# FAT35o.net
KiCad netlist of a schematic drawn in Altium Designer
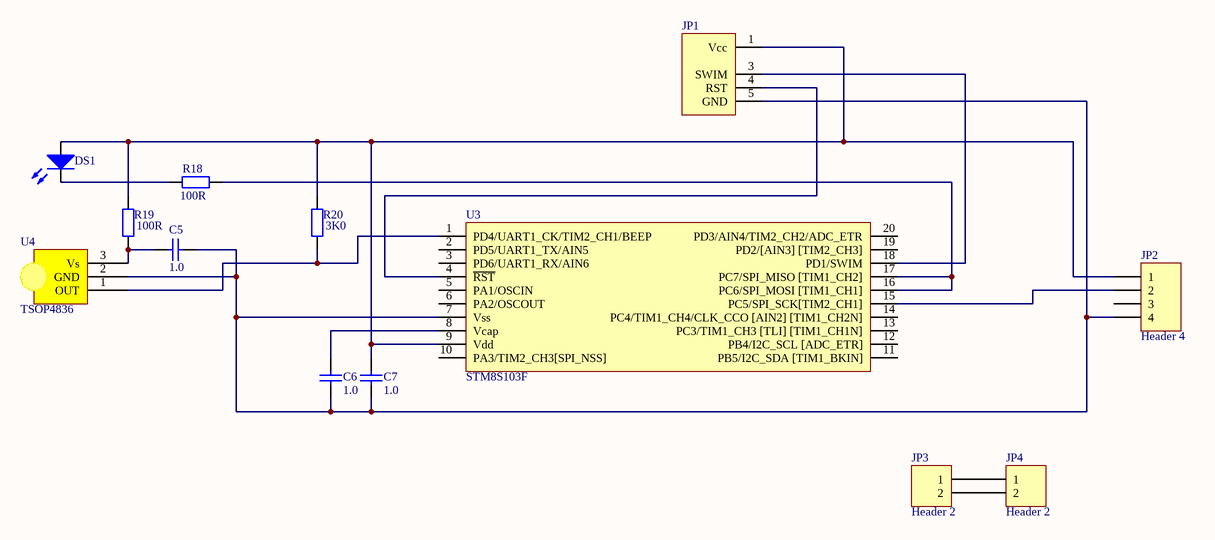
[diagram p0: FAT35o.SchDoc]

(export (version "E")
  (design (tool "Eeschema 10.0.6"))
  (components
    (comp (ref "C5")
      (value "1.0")
      (footprint "_1206")
      (description "Capacitor (Semiconductor SIM Model)")
      (fields (field (name "MANUFACTURER") "Generic Components") (field (name "PUBLISHER") "Altium Limited"))
      (libsource (lib "Miscellaneous Devices") (part "Cap Semi"))
    )
    (comp (ref "C6")
      (value "1.0")
      (footprint "_1206")
      (description "Capacitor (Semiconductor SIM Model)")
      (fields (field (name "MANUFACTURER") "Generic Components") (field (name "PUBLISHER") "Altium Limited"))
      (libsource (lib "") (part "Cap Semi_1"))
    )
    (comp (ref "C7")
      (value "1.0")
      (footprint "_1206")
      (description "Capacitor (Semiconductor SIM Model)")
      (fields (field (name "MANUFACTURER") "Generic Components") (field (name "PUBLISHER") "Altium Limited"))
      (libsource (lib "") (part "Cap Semi_1"))
    )
    (comp (ref "DS1")
      (value "~")
      (footprint "HDR1X2")
      (description "Typical INFRARED GaAs LED")
      (fields (field (name "MANUFACTURER") "Generic Components") (field (name "PUBLISHER") "Altium Limited"))
      (libsource (lib "PAL") (part "LED0"))
    )
    (comp (ref "JP1") (value "~") (footprint "HDR1X5_uart") (libsource (lib "PAL") (part "SWIM_CONN")))
    (comp (ref "JP2")
      (value "Header 4")
      (footprint "HDR2X2")
      (description "Header, 4-Pin")
      (fields (field (name "MANUFACTURER") "Generic Components") (field (name "PUBLISHER") "Altium Limited"))
      (libsource (lib "Miscellaneous Connectors") (part "Header 4"))
    )
    (comp (ref "JP3")
      (value "Header 2")
      (footprint "HDR1X2")
      (description "Header, 2-Pin")
      (fields (field (name "MANUFACTURER") "Generic Components") (field (name "PUBLISHER") "Altium Limited"))
      (libsource (lib "") (part "Header 2_1"))
    )
    (comp (ref "JP4")
      (value "Header 2")
      (footprint "HDR1X2")
      (description "Header, 2-Pin")
      (fields (field (name "MANUFACTURER") "Generic Components") (field (name "PUBLISHER") "Altium Limited"))
      (libsource (lib "Miscellaneous Connectors") (part "Header 2"))
    )
    (comp (ref "R18")
      (value "100R")
      (footprint "_1206")
      (description "Resistor")
      (fields (field (name "MANUFACTURER") "Generic Components") (field (name "PUBLISHER") "Altium Limited"))
      (libsource (lib "") (part "Res2_1"))
    )
    (comp (ref "R19")
      (value "100R")
      (footprint "_1206")
      (description "Resistor")
      (fields (field (name "MANUFACTURER") "Generic Components") (field (name "PUBLISHER") "Altium Limited"))
      (libsource (lib "Miscellaneous Devices") (part "Res2"))
    )
    (comp (ref "R20")
      (value "3K0")
      (footprint "_1206")
      (description "Resistor")
      (fields (field (name "MANUFACTURER") "Generic Components") (field (name "PUBLISHER") "Altium Limited"))
      (libsource (lib "Miscellaneous Devices") (part "Res2"))
    )
    (comp (ref "U3") (value "~") (footprint "TSSO6x6-G20/Y1.6") (libsource (lib "PAL") (part "STM8S103F")))
    (comp (ref "U4") (value "TSOP4836") (footprint "TSOP4836") (libsource (lib "PAL") (part "TSOP4836")))
  )
  (nets
    (net (code "1") (name "Net-(DS1-A)") (class "Default")
      (node (ref "C7") (pin "2") (pinfunction "2_2") (pintype "passive"))
      (node (ref "DS1") (pin "1") (pinfunction "A_1") (pintype "passive"))
      (node (ref "JP1") (pin "1") (pinfunction "Vcc_1") (pintype "passive"))
      (node (ref "JP2") (pin "1") (pinfunction "1_1") (pintype "passive"))
      (node (ref "R19") (pin "1") (pinfunction "1_1") (pintype "passive"))
      (node (ref "R20") (pin "1") (pinfunction "1_1") (pintype "passive"))
      (node (ref "U3") (pin "9") (pinfunction "Vdd_9") (pintype "passive"))
    )
    (net (code "2") (name "Net-(DS1-K)") (class "Default")
      (node (ref "DS1") (pin "2") (pinfunction "K_2") (pintype "passive"))
      (node (ref "R18") (pin "2") (pinfunction "2_2") (pintype "passive"))
    )
    (net (code "3") (name "Net-(JP1-GND)") (class "Default")
      (node (ref "C5") (pin "1") (pinfunction "1_1") (pintype "passive"))
      (node (ref "C6") (pin "1") (pinfunction "1_1") (pintype "passive"))
      (node (ref "C7") (pin "1") (pinfunction "1_1") (pintype "passive"))
      (node (ref "JP1") (pin "5") (pinfunction "GND_5") (pintype "passive"))
      (node (ref "JP2") (pin "4") (pinfunction "4_4") (pintype "passive"))
      (node (ref "U3") (pin "7") (pinfunction "Vss_7") (pintype "passive"))
      (node (ref "U4") (pin "2") (pinfunction "GND_2") (pintype "passive"))
    )
    (net (code "4") (name "Net-(JP1-RST)") (class "Default")
      (node (ref "JP1") (pin "4") (pinfunction "RST_4") (pintype "passive"))
      (node (ref "U3") (pin "4") (pinfunction "~{RST}_4") (pintype "passive"))
    )
    (net (code "5") (name "Net-(JP1-SWIM)") (class "Default")
      (node (ref "JP1") (pin "3") (pinfunction "SWIM_3") (pintype "passive"))
      (node (ref "U3") (pin "18") (pinfunction "PD1/SWIM_18") (pintype "passive"))
    )
    (net (code "6") (name "Net-(JP3-Pad1)") (class "Default")
      (node (ref "JP3") (pin "1") (pinfunction "1_1") (pintype "passive"))
      (node (ref "JP4") (pin "1") (pinfunction "1_1") (pintype "passive"))
    )
    (net (code "7") (name "Net-(JP3-Pad2)") (class "Default")
      (node (ref "JP3") (pin "2") (pinfunction "2_2") (pintype "passive"))
      (node (ref "JP4") (pin "2") (pinfunction "2_2") (pintype "passive"))
    )
    (net (code "8") (name "Net-(U3-PC5{slash}SPI_SCK[TIM2_CH1])") (class "Default")
      (node (ref "JP2") (pin "2") (pinfunction "2_2") (pintype "passive"))
      (node (ref "U3") (pin "15") (pinfunction "PC5/SPI_SCK[TIM2_CH1]_15") (pintype "passive"))
    )
    (net (code "9") (name "Net-(U3-PC6{slash}SPI_MOSI_[TIM1_CH1])") (class "Default")
      (node (ref "R18") (pin "1") (pinfunction "1_1") (pintype "passive"))
      (node (ref "U3") (pin "16") (pinfunction "PC6/SPI_MOSI_[TIM1_CH1]_16") (pintype "passive"))
      (node (ref "U3") (pin "17") (pinfunction "PC7/SPI_MISO_[TIM1_CH2]_17") (pintype "passive"))
    )
    (net (code "10") (name "Net-(U3-PD4{slash}UART1_CK{slash}TIM2_CH1{slash}BEEP)") (class "Default")
      (node (ref "R20") (pin "2") (pinfunction "2_2") (pintype "passive"))
      (node (ref "U3") (pin "1") (pinfunction "PD4/UART1_CK/TIM2_CH1/BEEP_1") (pintype "passive"))
      (node (ref "U4") (pin "1") (pinfunction "OUT_1") (pintype "passive"))
    )
    (net (code "11") (name "Net-(U3-Vcap)") (class "Default")
      (node (ref "C6") (pin "2") (pinfunction "2_2") (pintype "passive"))
      (node (ref "U3") (pin "8") (pinfunction "Vcap_8") (pintype "passive"))
    )
    (net (code "12") (name "Net-(U4-Vs)") (class "Default")
      (node (ref "C5") (pin "2") (pinfunction "2_2") (pintype "passive"))
      (node (ref "R19") (pin "2") (pinfunction "2_2") (pintype "passive"))
      (node (ref "U4") (pin "3") (pinfunction "Vs_3") (pintype "passive"))
    )
    (net (code "13") (name "unconnected-(JP2-Pad3)") (class "Default")
      (node (ref "JP2") (pin "3") (pinfunction "3_3") (pintype "passive"))
    )
    (net (code "14") (name "unconnected-(U3-PA1{slash}OSCIN-Pad5)") (class "Default")
      (node (ref "U3") (pin "5") (pinfunction "PA1/OSCIN_5") (pintype "passive"))
    )
    (net (code "15") (name "unconnected-(U3-PA2{slash}OSCOUT-Pad6)") (class "Default")
      (node (ref "U3") (pin "6") (pinfunction "PA2/OSCOUT_6") (pintype "passive"))
    )
    (net (code "16") (name "unconnected-(U3-PA3{slash}TIM2_CH3[SPI_NSS]-Pad10)") (class "Default")
      (node (ref "U3") (pin "10") (pinfunction "PA3/TIM2_CH3[SPI_NSS]_10") (pintype "passive"))
    )
    (net (code "17") (name "unconnected-(U3-PB4{slash}I2C_SCL_[ADC_ETR]-Pad12)") (class "Default")
      (node (ref "U3") (pin "12") (pinfunction "PB4/I2C_SCL_[ADC_ETR]_12") (pintype "passive"))
    )
    (net (code "18") (name "unconnected-(U3-PB5{slash}I2C_SDA_[TIM1_BKIN]-Pad11)") (class "Default")
      (node (ref "U3") (pin "11") (pinfunction "PB5/I2C_SDA_[TIM1_BKIN]_11") (pintype "passive"))
    )
    (net (code "19") (name "unconnected-(U3-PC3{slash}TIM1_CH3_[TLI]_[TIM1_CH1N]-Pad13)") (class "Default")
      (node (ref "U3") (pin "13") (pinfunction "PC3/TIM1_CH3_[TLI]_[TIM1_CH1N]_13") (pintype "passive"))
    )
    (net (code "20") (name "unconnected-(U3-PC4{slash}TIM1_CH4{slash}CLK_CCO_[AIN2]_[TIM1_CH2N]-Pad14)") (class "Default")
      (node (ref "U3") (pin "14") (pinfunction "PC4/TIM1_CH4/CLK_CCO_[AIN2]_[TIM1_CH2N]_14") (pintype "passive"))
    )
    (net (code "21") (name "unconnected-(U3-PD2{slash}[AIN3]_[TIM2_CH3]-Pad19)") (class "Default")
      (node (ref "U3") (pin "19") (pinfunction "PD2/[AIN3]_[TIM2_CH3]_19") (pintype "passive"))
    )
    (net (code "22") (name "unconnected-(U3-PD3{slash}AIN4{slash}TIM2_CH2{slash}ADC_ETR-Pad20)") (class "Default")
      (node (ref "U3") (pin "20") (pinfunction "PD3/AIN4/TIM2_CH2/ADC_ETR_20") (pintype "passive"))
    )
    (net (code "23") (name "unconnected-(U3-PD5{slash}UART1_TX{slash}AIN5-Pad2)") (class "Default")
      (node (ref "U3") (pin "2") (pinfunction "PD5/UART1_TX/AIN5_2") (pintype "passive"))
    )
    (net (code "24") (name "unconnected-(U3-PD6{slash}UART1_RX{slash}AIN6-Pad3)") (class "Default")
      (node (ref "U3") (pin "3") (pinfunction "PD6/UART1_RX/AIN6_3") (pintype "passive"))
    )
  )
)
